# Current_Driver_v2.net
KiCad netlist of a schematic drawn in EAGLE
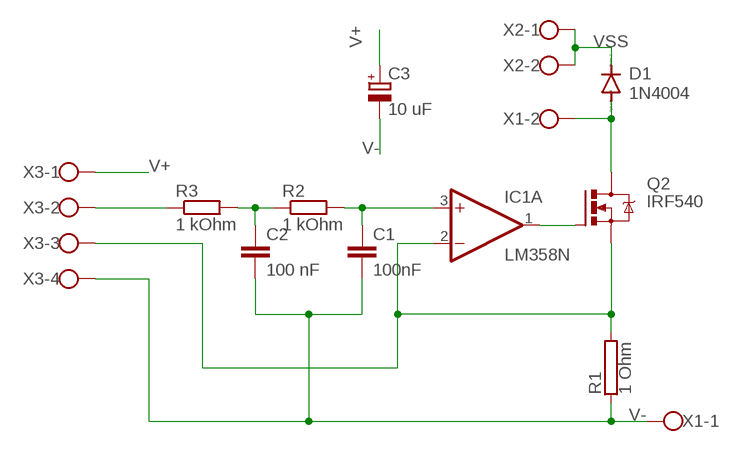
[diagram p0: schematic, sheet 1]

(export (version "E")
  (design (tool "Eeschema 10.0.6"))
  (components
    (comp (ref "C1")
      (value "100nF")
      (footprint "eagle-import:C050-030X075")
      (libsource (lib "eagle-import") (part "C-EU050-030X075"))
    )
    (comp (ref "C2")
      (value "100 nF")
      (footprint "eagle-import:C050-030X075")
      (libsource (lib "eagle-import") (part "C-EU050-030X075"))
    )
    (comp (ref "C3")
      (value "10 uF")
      (footprint "eagle-import:E2,5-6E")
      (libsource (lib "eagle-import") (part "CPOL-EUE2,5-6E"))
    )
    (comp (ref "D1")
      (value "1N4004")
      (footprint "eagle-import:DO41-10")
      (libsource (lib "eagle-import") (part "1N4004"))
    )
    (comp (ref "IC1")
      (value "LM358N")
      (footprint "eagle-import:DIL08")
      (libsource (lib "eagle-import") (part "LM358N"))
    )
    (comp (ref "Q2")
      (value "IRF540")
      (footprint "eagle-import:TO220BV")
      (libsource (lib "eagle-import") (part "IRF540"))
    )
    (comp (ref "R1")
      (value "1 Ohm")
      (footprint "eagle-import:AC05")
      (libsource (lib "eagle-import") (part "RAC05"))
    )
    (comp (ref "R2")
      (value "1 kOhm")
      (footprint "eagle-import:0204_7")
      (libsource (lib "eagle-import") (part "R-EU_0204/7"))
    )
    (comp (ref "R3")
      (value "1 kOhm")
      (footprint "eagle-import:0204_7")
      (libsource (lib "eagle-import") (part "R-EU_0204/7"))
    )
    (comp (ref "X1")
      (value "W237-102")
      (footprint "eagle-import:W237-102")
      (fields (field (name "MPN") "237-102"))
      (libsource (lib "eagle-import") (part "W237-102"))
    )
    (comp (ref "X2")
      (value "W237-102")
      (footprint "eagle-import:W237-102")
      (fields (field (name "MPN") "237-102"))
      (libsource (lib "eagle-import") (part "W237-102"))
    )
    (comp (ref "X3")
      (value "W237-4")
      (footprint "eagle-import:W237-4")
      (libsource (lib "eagle-import") (part "W237-4"))
    )
  )
  (nets
    (net (code "1") (name "/V+") (class "Default")
      (node (ref "C3") (pin "+") (pinfunction "+_+") (pintype "passive"))
      (node (ref "X3") (pin "1") (pinfunction "KL_1") (pintype "passive"))
    )
    (net (code "2") (name "/V-") (class "Default")
      (node (ref "C1") (pin "2") (pinfunction "2_2") (pintype "passive"))
      (node (ref "C2") (pin "2") (pinfunction "2_2") (pintype "passive"))
      (node (ref "C3") (pin "-") (pinfunction "-_-") (pintype "passive"))
      (node (ref "R1") (pin "1") (pinfunction "1_1") (pintype "passive"))
      (node (ref "X1") (pin "1") (pinfunction "KL_1") (pintype "passive"))
      (node (ref "X3") (pin "4") (pinfunction "KL_4") (pintype "passive"))
    )
    (net (code "3") (name "/VSS") (class "Default")
      (node (ref "D1") (pin "C") (pinfunction "C_C") (pintype "passive"))
      (node (ref "X2") (pin "1") (pinfunction "KL_1") (pintype "passive"))
      (node (ref "X2") (pin "2") (pinfunction "KL_2") (pintype "passive"))
    )
    (net (code "4") (name "Net-(C2-Pad1)") (class "Default")
      (node (ref "C2") (pin "1") (pinfunction "1_1") (pintype "passive"))
      (node (ref "R2") (pin "1") (pinfunction "1_1") (pintype "passive"))
      (node (ref "R3") (pin "2") (pinfunction "2_2") (pintype "passive"))
    )
    (net (code "5") (name "Net-(IC1A-+IN)") (class "Default")
      (node (ref "C1") (pin "1") (pinfunction "1_1") (pintype "passive"))
      (node (ref "IC1") (pin "3") (pinfunction "+IN_3") (pintype "input"))
      (node (ref "R2") (pin "2") (pinfunction "2_2") (pintype "passive"))
    )
    (net (code "6") (name "Net-(IC1A--IN)") (class "Default")
      (node (ref "IC1") (pin "2") (pinfunction "-IN_2") (pintype "input"))
      (node (ref "Q2") (pin "S") (pinfunction "S_S") (pintype "passive"))
      (node (ref "R1") (pin "2") (pinfunction "2_2") (pintype "passive"))
      (node (ref "X3") (pin "3") (pinfunction "KL_3") (pintype "passive"))
    )
    (net (code "7") (name "Net-(IC1A-OUT)") (class "Default")
      (node (ref "IC1") (pin "1") (pinfunction "OUT_1") (pintype "output"))
      (node (ref "Q2") (pin "G") (pinfunction "G_G") (pintype "passive"))
    )
    (net (code "8") (name "Net-(X1B-KL)") (class "Default")
      (node (ref "D1") (pin "A") (pinfunction "A_A") (pintype "passive"))
      (node (ref "Q2") (pin "D") (pinfunction "D_D") (pintype "passive"))
      (node (ref "X1") (pin "2") (pinfunction "KL_2") (pintype "passive"))
    )
    (net (code "9") (name "Net-(X3B-KL)") (class "Default")
      (node (ref "R3") (pin "1") (pinfunction "1_1") (pintype "passive"))
      (node (ref "X3") (pin "2") (pinfunction "KL_2") (pintype "passive"))
    )
  )
)
